# 2_MCU.net
KiCad netlist of a schematic drawn in Altium Designer
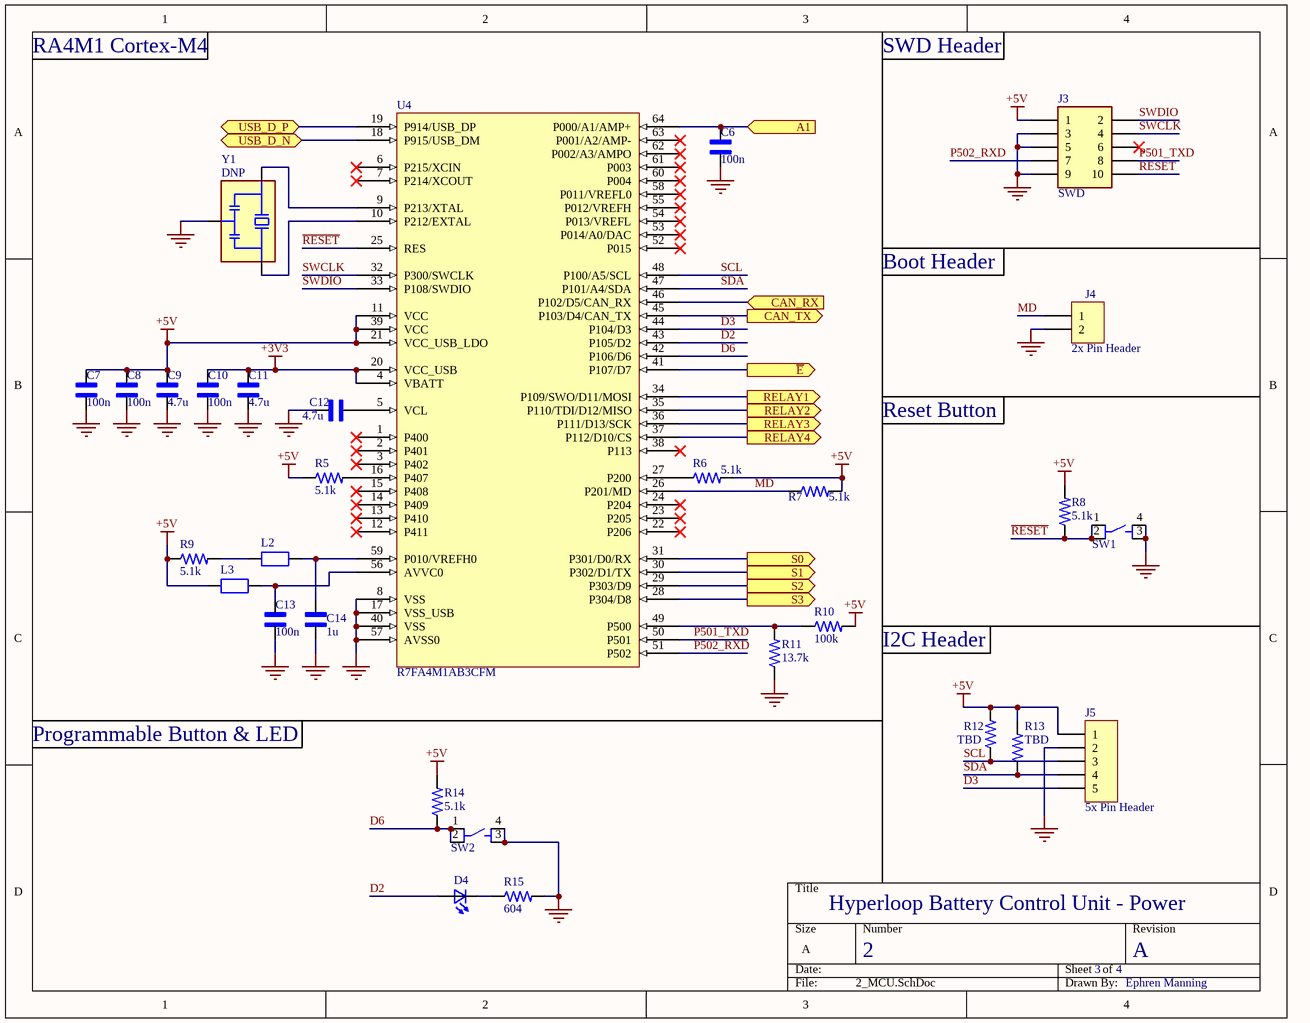
[diagram p0: 2_MCU.SchDoc]

(export (version "E")
  (design (tool "Eeschema 10.0.6"))
  (components
    (comp (ref "C6")
      (value "100n")
      (footprint "CAP_0603-Footprint")
      (description "100nF/16V ±10% Ceramic 0603")
      (libsource (lib "SAE @ UIC Formula Electric") (part "CAP_0603-Symbol"))
    )
    (comp (ref "C7")
      (value "100n")
      (footprint "CAP_0603-Footprint")
      (description "100nF/16V ±10% Ceramic 0603")
      (libsource (lib "SAE @ UIC Formula Electric") (part "CAP_0603-Symbol"))
    )
    (comp (ref "C8")
      (value "100n")
      (footprint "CAP_0603-Footprint")
      (description "100nF/16V ±10% Ceramic 0603")
      (libsource (lib "SAE @ UIC Formula Electric") (part "CAP_0603-Symbol"))
    )
    (comp (ref "C9")
      (value "4.7u")
      (footprint "CAP_0603-Footprint")
      (description "4.7uF/10V 0603 Ceramic Capacitor")
      (libsource (lib "SAE @ UIC Formula Electric") (part "CAP_0603-Symbol"))
    )
    (comp (ref "C10")
      (value "100n")
      (footprint "CAP_0603-Footprint")
      (description "100nF/16V ±10% Ceramic 0603")
      (libsource (lib "SAE @ UIC Formula Electric") (part "CAP_0603-Symbol"))
    )
    (comp (ref "C11")
      (value "4.7u")
      (footprint "CAP_0603-Footprint")
      (description "4.7uF/10V 0603 Ceramic Capacitor")
      (libsource (lib "SAE @ UIC Formula Electric") (part "CAP_0603-Symbol"))
    )
    (comp (ref "C12")
      (value "4.7u")
      (footprint "CAP_0603-Footprint")
      (description "4.7uF/10V 0603 Ceramic Capacitor")
      (libsource (lib "") (part "CAP_0603-Symbol_1"))
    )
    (comp (ref "C13")
      (value "100n")
      (footprint "CAP_0603-Footprint")
      (description "100nF/16V ±10% Ceramic 0603")
      (libsource (lib "SAE @ UIC Formula Electric") (part "CAP_0603-Symbol"))
    )
    (comp (ref "C14")
      (value "1u")
      (footprint "CAP_0603-Footprint")
      (description "1uF/10V ±10% 0603")
      (libsource (lib "SAE @ UIC Formula Electric") (part "CAP_0603-Symbol"))
    )
    (comp (ref "D4")
      (value "LTST-C191KGKT")
      (footprint "LED_0603-Footprint-1")
      (description "Green 571nm LED Indication - Discrete 2V 0603 (1608 Metric)")
      (libsource (lib "SAE @ UIC Formula Electric") (part "LTST-C191KGKT"))
    )
    (comp (ref "J3")
      (value "SWD")
      (footprint "CNC_3221-10-0100-00")
      (description "SWD Connector")
      (libsource (lib "SAE @ UIC Formula Electric") (part "3221-10-0100-00"))
    )
    (comp (ref "J4")
      (value "2x Pin Header")
      (footprint "2x Pin Header-Footprint-1")
      (libsource (lib "SAE @ UIC Formula Electric") (part "2x Pin Header-Symbol-1"))
    )
    (comp (ref "J5")
      (value "5x Pin Header")
      (footprint "5x Pin Header-Footprint-1")
      (libsource (lib "SAE @ UIC Formula Electric") (part "5x Pin Header-Symbol-1"))
    )
    (comp (ref "L2")
      (value "BLM18PG471SN1D")
      (footprint "BEADC1608X95N")
      (description "Ferrite Bead, 0603, 470 Ohms @ 100MHz")
      (libsource (lib "SAE @ UIC Formula Electric") (part "BLM18PG471SN1D"))
    )
    (comp (ref "L3")
      (value "BLM18PG471SN1D")
      (footprint "BEADC1608X95N")
      (description "Ferrite Bead, 0603, 470 Ohms @ 100MHz")
      (libsource (lib "SAE @ UIC Formula Electric") (part "BLM18PG471SN1D"))
    )
    (comp (ref "R5")
      (value "5.1k")
      (footprint "RES_0603-Footprint-1")
      (description "5.1k Ohms ±1% 0.1W 0603")
      (libsource (lib "SAE @ UIC Formula Electric") (part "0603_Res"))
    )
    (comp (ref "R6")
      (value "5.1k")
      (footprint "RES_0603-Footprint-1")
      (description "5.1k Ohms ±1% 0.1W 0603")
      (libsource (lib "SAE @ UIC Formula Electric") (part "0603_Res"))
    )
    (comp (ref "R7")
      (value "5.1k")
      (footprint "RES_0603-Footprint-1")
      (description "5.1k Ohms ±1% 0.1W 0603")
      (libsource (lib "SAE @ UIC Formula Electric") (part "0603_Res"))
    )
    (comp (ref "R8")
      (value "5.1k")
      (footprint "RES_0603-Footprint-1")
      (description "5.1k Ohms ±1% 0.1W 0603")
      (libsource (lib "SAE @ UIC Formula Electric") (part "0603_Res"))
    )
    (comp (ref "R9")
      (value "5.1k")
      (footprint "RES_0603-Footprint-1")
      (description "5.1k Ohms ±1% 0.1W 0603")
      (libsource (lib "SAE @ UIC Formula Electric") (part "0603_Res"))
    )
    (comp (ref "R10")
      (value "100k")
      (footprint "RES_0603-Footprint-1")
      (description "100k ±1% 0.1W, 0603")
      (libsource (lib "SAE @ UIC Formula Electric") (part "0603_Res"))
    )
    (comp (ref "R11")
      (value "13.7k")
      (footprint "RES_0603-Footprint-1")
      (description "13.7K 1% 0,1W 0603")
      (libsource (lib "SAE @ UIC Formula Electric") (part "0603_Res"))
    )
    (comp (ref "R12")
      (value "TBD")
      (footprint "RES_0603-Footprint-1")
      (description "5.1k Ohms ±1% 0.1W 0603")
      (libsource (lib "SAE @ UIC Formula Electric") (part "0603_Res"))
    )
    (comp (ref "R13")
      (value "TBD")
      (footprint "RES_0603-Footprint-1")
      (description "5.1k Ohms ±1% 0.1W 0603")
      (libsource (lib "SAE @ UIC Formula Electric") (part "0603_Res"))
    )
    (comp (ref "R14")
      (value "5.1k")
      (footprint "RES_0603-Footprint-1")
      (description "5.1k Ohms ±1% 0.1W 0603")
      (libsource (lib "SAE @ UIC Formula Electric") (part "0603_Res"))
    )
    (comp (ref "R15")
      (value "604")
      (footprint "RES_0603-Footprint-1")
      (description "604 Ohm 1% 1/10 W 0603")
      (libsource (lib "SAE @ UIC Formula Electric") (part "0603_Res"))
    )
    (comp (ref "SW1")
      (value "PTS810_SJM_250_SMTR_LFS")
      (footprint "SW_PTS810_SJM_250_SMTR_LFS")
      (description "Tactile Switch SPST-NO Top Actuated Surface Mount")
      (libsource (lib "SAE @ UIC Formula Electric") (part "PTS810_SJM_250_SMTR_LFS"))
    )
    (comp (ref "SW2")
      (value "PTS810_SJM_250_SMTR_LFS")
      (footprint "SW_PTS810_SJM_250_SMTR_LFS")
      (description "Tactile Switch SPST-NO Top Actuated Surface Mount")
      (libsource (lib "SAE @ UIC Formula Electric") (part "PTS810_SJM_250_SMTR_LFS"))
    )
    (comp (ref "U4")
      (value "R7FA4M1AB3CFM")
      (footprint "R7FA4M1AB3CFM-Footprint-1")
      (description "RA4M1 Cortex-M4 Microcontroller 64-LQFP")
      (libsource (lib "SAE @ UIC Formula Electric") (part "R7FA4M1AB3CFM-Symbol-1"))
    )
    (comp (ref "Y1")
      (value "DNP")
      (footprint "OSC_CSTNE12M0G55Z000R0")
      (description "12MHz Ceramic Resonator Built in Capacitor 33pF ±0.2% 30 Ohms Surface Mount")
      (libsource (lib "SAE @ UIC Formula Electric") (part "CSTNE12M0G55Z000R0"))
    )
  )
  (nets
    (net (code "1") (name "+3V3") (class "Default")
      (node (ref "C10") (pin "2") (pinfunction "2_2") (pintype "passive"))
      (node (ref "C11") (pin "2") (pinfunction "2_2") (pintype "passive"))
      (node (ref "U4") (pin "20") (pinfunction "VCC_USB_20") (pintype "input"))
      (node (ref "U4") (pin "4") (pinfunction "VBATT_4") (pintype "input"))
    )
    (net (code "2") (name "+5V") (class "Default")
      (node (ref "C7") (pin "2") (pinfunction "2_2") (pintype "passive"))
      (node (ref "C8") (pin "2") (pinfunction "2_2") (pintype "passive"))
      (node (ref "C9") (pin "2") (pinfunction "2_2") (pintype "passive"))
      (node (ref "J3") (pin "1") (pinfunction "1_1") (pintype "passive"))
      (node (ref "J5") (pin "1") (pinfunction "1_1") (pintype "passive"))
      (node (ref "L3") (pin "1") (pinfunction "1_1") (pintype "passive"))
      (node (ref "R10") (pin "2") (pinfunction "2_2") (pintype "passive"))
      (node (ref "R12") (pin "2") (pinfunction "2_2") (pintype "passive"))
      (node (ref "R13") (pin "2") (pinfunction "2_2") (pintype "passive"))
      (node (ref "R14") (pin "2") (pinfunction "2_2") (pintype "passive"))
      (node (ref "R5") (pin "1") (pinfunction "1_1") (pintype "passive"))
      (node (ref "R6") (pin "2") (pinfunction "2_2") (pintype "passive"))
      (node (ref "R7") (pin "2") (pinfunction "2_2") (pintype "passive"))
      (node (ref "R8") (pin "2") (pinfunction "2_2") (pintype "passive"))
      (node (ref "R9") (pin "1") (pinfunction "1_1") (pintype "passive"))
      (node (ref "U4") (pin "11") (pinfunction "VCC_11") (pintype "input"))
      (node (ref "U4") (pin "21") (pinfunction "VCC_USB_LDO_21") (pintype "input"))
      (node (ref "U4") (pin "39") (pinfunction "VCC_39") (pintype "input"))
    )
    (net (code "3") (name "/A1") (class "Default")
      (node (ref "C6") (pin "2") (pinfunction "2_2") (pintype "passive"))
      (node (ref "U4") (pin "64") (pinfunction "P000/A1/AMP+_64") (pintype "input"))
    )
    (net (code "4") (name "/CAN_RX") (class "Default")
      (node (ref "U4") (pin "46") (pinfunction "P102/D5/CAN_RX_46") (pintype "input"))
    )
    (net (code "5") (name "/CAN_TX") (class "Default")
      (node (ref "U4") (pin "45") (pinfunction "P103/D4/CAN_TX_45") (pintype "input"))
    )
    (net (code "6") (name "/D2") (class "Default")
      (node (ref "D4") (pin "2") (pinfunction "A2_2") (pintype "passive"))
      (node (ref "U4") (pin "43") (pinfunction "P105/D2_43") (pintype "input"))
    )
    (net (code "7") (name "/D3") (class "Default")
      (node (ref "J5") (pin "5") (pinfunction "5_5") (pintype "passive"))
      (node (ref "U4") (pin "44") (pinfunction "P104/D3_44") (pintype "input"))
    )
    (net (code "8") (name "/D6") (class "Default")
      (node (ref "R14") (pin "1") (pinfunction "1_1") (pintype "passive"))
      (node (ref "SW2") (pin "1") (pinfunction "1_1") (pintype "passive"))
      (node (ref "SW2") (pin "2") (pinfunction "2_2") (pintype "passive"))
      (node (ref "U4") (pin "42") (pinfunction "P106/D6_42") (pintype "input"))
    )
    (net (code "9") (name "/MD") (class "Default")
      (node (ref "J4") (pin "1") (pinfunction "1_1") (pintype "passive"))
      (node (ref "R7") (pin "1") (pinfunction "1_1") (pintype "passive"))
      (node (ref "U4") (pin "26") (pinfunction "P201/MD_26") (pintype "input"))
    )
    (net (code "10") (name "/P501_TXD") (class "Default")
      (node (ref "J3") (pin "8") (pinfunction "8_8") (pintype "passive"))
      (node (ref "U4") (pin "50") (pinfunction "P501_50") (pintype "input"))
    )
    (net (code "11") (name "/P502_RXD") (class "Default")
      (node (ref "J3") (pin "7") (pinfunction "7_7") (pintype "passive"))
      (node (ref "U4") (pin "51") (pinfunction "P502_51") (pintype "input"))
    )
    (net (code "12") (name "/RELAY1") (class "Default")
      (node (ref "U4") (pin "34") (pinfunction "P109/SWO/D11/MOSI_34") (pintype "input"))
    )
    (net (code "13") (name "/RELAY2") (class "Default")
      (node (ref "U4") (pin "35") (pinfunction "P110/TDI/D12/MISO_35") (pintype "input"))
    )
    (net (code "14") (name "/RELAY3") (class "Default")
      (node (ref "U4") (pin "36") (pinfunction "P111/D13/SCK_36") (pintype "input"))
    )
    (net (code "15") (name "/RELAY4") (class "Default")
      (node (ref "U4") (pin "37") (pinfunction "P112/D10/CS_37") (pintype "input"))
    )
    (net (code "16") (name "/S0") (class "Default")
      (node (ref "U4") (pin "31") (pinfunction "P301/D0/RX_31") (pintype "input"))
    )
    (net (code "17") (name "/S1") (class "Default")
      (node (ref "U4") (pin "30") (pinfunction "P302/D1/TX_30") (pintype "input"))
    )
    (net (code "18") (name "/S2") (class "Default")
      (node (ref "U4") (pin "29") (pinfunction "P303/D9_29") (pintype "input"))
    )
    (net (code "19") (name "/S3") (class "Default")
      (node (ref "U4") (pin "28") (pinfunction "P304/D8_28") (pintype "input"))
    )
    (net (code "20") (name "/SCL") (class "Default")
      (node (ref "J5") (pin "3") (pinfunction "3_3") (pintype "passive"))
      (node (ref "R12") (pin "1") (pinfunction "1_1") (pintype "passive"))
      (node (ref "U4") (pin "48") (pinfunction "P100/A5/SCL_48") (pintype "input"))
    )
    (net (code "21") (name "/SDA") (class "Default")
      (node (ref "J5") (pin "4") (pinfunction "4_4") (pintype "passive"))
      (node (ref "R13") (pin "1") (pinfunction "1_1") (pintype "passive"))
      (node (ref "U4") (pin "47") (pinfunction "P101/A4/SDA_47") (pintype "input"))
    )
    (net (code "22") (name "/SWCLK") (class "Default")
      (node (ref "J3") (pin "4") (pinfunction "4_4") (pintype "passive"))
      (node (ref "U4") (pin "32") (pinfunction "P300/SWCLK_32") (pintype "input"))
    )
    (net (code "23") (name "/SWDIO") (class "Default")
      (node (ref "J3") (pin "2") (pinfunction "2_2") (pintype "passive"))
      (node (ref "U4") (pin "33") (pinfunction "P108/SWDIO_33") (pintype "input"))
    )
    (net (code "24") (name "/USB_D_N") (class "Default")
      (node (ref "U4") (pin "18") (pinfunction "P915/USB_DM_18") (pintype "input"))
    )
    (net (code "25") (name "/USB_D_P") (class "Default")
      (node (ref "U4") (pin "19") (pinfunction "P914/USB_DP_19") (pintype "input"))
    )
    (net (code "26") (name "/~{E}") (class "Default")
      (node (ref "U4") (pin "41") (pinfunction "P107/D7_41") (pintype "input"))
    )
    (net (code "27") (name "/~{RESET}") (class "Default")
      (node (ref "J3") (pin "10") (pinfunction "10_10") (pintype "passive"))
      (node (ref "R8") (pin "1") (pinfunction "1_1") (pintype "passive"))
      (node (ref "SW1") (pin "1") (pinfunction "1_1") (pintype "passive"))
      (node (ref "SW1") (pin "2") (pinfunction "2_2") (pintype "passive"))
      (node (ref "U4") (pin "25") (pinfunction "RES_25") (pintype "input"))
    )
    (net (code "28") (name "GND") (class "Default")
      (node (ref "C10") (pin "1") (pinfunction "1_1") (pintype "passive"))
      (node (ref "C11") (pin "1") (pinfunction "1_1") (pintype "passive"))
      (node (ref "C12") (pin "1") (pinfunction "1_1") (pintype "passive"))
      (node (ref "C13") (pin "1") (pinfunction "1_1") (pintype "passive"))
      (node (ref "C14") (pin "1") (pinfunction "1_1") (pintype "passive"))
      (node (ref "C6") (pin "1") (pinfunction "1_1") (pintype "passive"))
      (node (ref "C7") (pin "1") (pinfunction "1_1") (pintype "passive"))
      (node (ref "C8") (pin "1") (pinfunction "1_1") (pintype "passive"))
      (node (ref "C9") (pin "1") (pinfunction "1_1") (pintype "passive"))
      (node (ref "J3") (pin "3") (pinfunction "3_3") (pintype "passive"))
      (node (ref "J3") (pin "5") (pinfunction "5_5") (pintype "passive"))
      (node (ref "J3") (pin "9") (pinfunction "9_9") (pintype "passive"))
      (node (ref "J4") (pin "2") (pinfunction "2_2") (pintype "passive"))
      (node (ref "J5") (pin "2") (pinfunction "2_2") (pintype "passive"))
      (node (ref "R11") (pin "1") (pinfunction "1_1") (pintype "passive"))
      (node (ref "R15") (pin "2") (pinfunction "2_2") (pintype "passive"))
      (node (ref "SW1") (pin "3") (pinfunction "3_3") (pintype "passive"))
      (node (ref "SW1") (pin "4") (pinfunction "4_4") (pintype "passive"))
      (node (ref "SW2") (pin "3") (pinfunction "3_3") (pintype "passive"))
      (node (ref "SW2") (pin "4") (pinfunction "4_4") (pintype "passive"))
      (node (ref "U4") (pin "17") (pinfunction "VSS_USB_17") (pintype "input"))
      (node (ref "U4") (pin "40") (pinfunction "VSS_40") (pintype "input"))
      (node (ref "U4") (pin "57") (pinfunction "AVSS0_57") (pintype "input"))
      (node (ref "U4") (pin "8") (pinfunction "VSS_8") (pintype "input"))
      (node (ref "Y1") (pin "2") (pinfunction "GND_2") (pintype "power_in"))
    )
    (net (code "29") (name "Net-(D4-K2)") (class "Default")
      (node (ref "D4") (pin "1") (pinfunction "K2_1") (pintype "passive"))
      (node (ref "R15") (pin "1") (pinfunction "1_1") (pintype "passive"))
    )
    (net (code "30") (name "Net-(L2-Pad1)") (class "Default")
      (node (ref "L2") (pin "1") (pinfunction "1_1") (pintype "passive"))
      (node (ref "R9") (pin "2") (pinfunction "2_2") (pintype "passive"))
    )
    (net (code "31") (name "Net-(U4-AVVC0)") (class "Default")
      (node (ref "C13") (pin "2") (pinfunction "2_2") (pintype "passive"))
      (node (ref "L3") (pin "2") (pinfunction "2_2") (pintype "passive"))
      (node (ref "U4") (pin "56") (pinfunction "AVVC0_56") (pintype "input"))
    )
    (net (code "32") (name "Net-(U4-P010{slash}VREFH0)") (class "Default")
      (node (ref "C14") (pin "2") (pinfunction "2_2") (pintype "passive"))
      (node (ref "L2") (pin "2") (pinfunction "2_2") (pintype "passive"))
      (node (ref "U4") (pin "59") (pinfunction "P010/VREFH0_59") (pintype "input"))
    )
    (net (code "33") (name "Net-(U4-P200)") (class "Default")
      (node (ref "R6") (pin "1") (pinfunction "1_1") (pintype "passive"))
      (node (ref "U4") (pin "27") (pinfunction "P200_27") (pintype "input"))
    )
    (net (code "34") (name "Net-(U4-P212{slash}EXTAL)") (class "Default")
      (node (ref "U4") (pin "10") (pinfunction "P212/EXTAL_10") (pintype "input"))
      (node (ref "Y1") (pin "3") (pinfunction "OUT_3") (pintype "passive"))
    )
    (net (code "35") (name "Net-(U4-P213{slash}XTAL)") (class "Default")
      (node (ref "U4") (pin "9") (pinfunction "P213/XTAL_9") (pintype "input"))
      (node (ref "Y1") (pin "1") (pinfunction "IN_1") (pintype "passive"))
    )
    (net (code "36") (name "Net-(U4-P407)") (class "Default")
      (node (ref "R5") (pin "2") (pinfunction "2_2") (pintype "passive"))
      (node (ref "U4") (pin "16") (pinfunction "P407_16") (pintype "input"))
    )
    (net (code "37") (name "Net-(U4-P500)") (class "Default")
      (node (ref "R10") (pin "1") (pinfunction "1_1") (pintype "passive"))
      (node (ref "R11") (pin "2") (pinfunction "2_2") (pintype "passive"))
      (node (ref "U4") (pin "49") (pinfunction "P500_49") (pintype "input"))
    )
    (net (code "38") (name "Net-(U4-VCL)") (class "Default")
      (node (ref "C12") (pin "2") (pinfunction "2_2") (pintype "passive"))
      (node (ref "U4") (pin "5") (pinfunction "VCL_5") (pintype "input"))
    )
    (net (code "39") (name "unconnected-(J3-Pad6)") (class "Default")
      (node (ref "J3") (pin "6") (pinfunction "6_6") (pintype "passive+no_connect"))
    )
    (net (code "40") (name "unconnected-(U4-P001{slash}A2{slash}AMP--Pad63)") (class "Default")
      (node (ref "U4") (pin "63") (pinfunction "P001/A2/AMP-_63") (pintype "input+no_connect"))
    )
    (net (code "41") (name "unconnected-(U4-P002{slash}A3{slash}AMPO-Pad62)") (class "Default")
      (node (ref "U4") (pin "62") (pinfunction "P002/A3/AMPO_62") (pintype "input+no_connect"))
    )
    (net (code "42") (name "unconnected-(U4-P003-Pad61)") (class "Default")
      (node (ref "U4") (pin "61") (pinfunction "P003_61") (pintype "input+no_connect"))
    )
    (net (code "43") (name "unconnected-(U4-P004-Pad60)") (class "Default")
      (node (ref "U4") (pin "60") (pinfunction "P004_60") (pintype "input+no_connect"))
    )
    (net (code "44") (name "unconnected-(U4-P011{slash}VREFL0-Pad58)") (class "Default")
      (node (ref "U4") (pin "58") (pinfunction "P011/VREFL0_58") (pintype "input+no_connect"))
    )
    (net (code "45") (name "unconnected-(U4-P012{slash}VREFH-Pad55)") (class "Default")
      (node (ref "U4") (pin "55") (pinfunction "P012/VREFH_55") (pintype "input+no_connect"))
    )
    (net (code "46") (name "unconnected-(U4-P013{slash}VREFL-Pad54)") (class "Default")
      (node (ref "U4") (pin "54") (pinfunction "P013/VREFL_54") (pintype "input+no_connect"))
    )
    (net (code "47") (name "unconnected-(U4-P014{slash}A0{slash}DAC-Pad53)") (class "Default")
      (node (ref "U4") (pin "53") (pinfunction "P014/A0/DAC_53") (pintype "input+no_connect"))
    )
    (net (code "48") (name "unconnected-(U4-P015-Pad52)") (class "Default")
      (node (ref "U4") (pin "52") (pinfunction "P015_52") (pintype "input+no_connect"))
    )
    (net (code "49") (name "unconnected-(U4-P113-Pad38)") (class "Default")
      (node (ref "U4") (pin "38") (pinfunction "P113_38") (pintype "input+no_connect"))
    )
    (net (code "50") (name "unconnected-(U4-P204-Pad24)") (class "Default")
      (node (ref "U4") (pin "24") (pinfunction "P204_24") (pintype "input+no_connect"))
    )
    (net (code "51") (name "unconnected-(U4-P205-Pad23)") (class "Default")
      (node (ref "U4") (pin "23") (pinfunction "P205_23") (pintype "input+no_connect"))
    )
    (net (code "52") (name "unconnected-(U4-P206-Pad22)") (class "Default")
      (node (ref "U4") (pin "22") (pinfunction "P206_22") (pintype "input+no_connect"))
    )
    (net (code "53") (name "unconnected-(U4-P214{slash}XCOUT-Pad7)") (class "Default")
      (node (ref "U4") (pin "7") (pinfunction "P214/XCOUT_7") (pintype "input+no_connect"))
    )
    (net (code "54") (name "unconnected-(U4-P215{slash}XCIN-Pad6)") (class "Default")
      (node (ref "U4") (pin "6") (pinfunction "P215/XCIN_6") (pintype "input+no_connect"))
    )
    (net (code "55") (name "unconnected-(U4-P400-Pad1)") (class "Default")
      (node (ref "U4") (pin "1") (pinfunction "P400_1") (pintype "input+no_connect"))
    )
    (net (code "56") (name "unconnected-(U4-P401-Pad2)") (class "Default")
      (node (ref "U4") (pin "2") (pinfunction "P401_2") (pintype "input+no_connect"))
    )
    (net (code "57") (name "unconnected-(U4-P402-Pad3)") (class "Default")
      (node (ref "U4") (pin "3") (pinfunction "P402_3") (pintype "input+no_connect"))
    )
    (net (code "58") (name "unconnected-(U4-P408-Pad15)") (class "Default")
      (node (ref "U4") (pin "15") (pinfunction "P408_15") (pintype "input+no_connect"))
    )
    (net (code "59") (name "unconnected-(U4-P409-Pad14)") (class "Default")
      (node (ref "U4") (pin "14") (pinfunction "P409_14") (pintype "input+no_connect"))
    )
    (net (code "60") (name "unconnected-(U4-P410-Pad13)") (class "Default")
      (node (ref "U4") (pin "13") (pinfunction "P410_13") (pintype "input+no_connect"))
    )
    (net (code "61") (name "unconnected-(U4-P411-Pad12)") (class "Default")
      (node (ref "U4") (pin "12") (pinfunction "P411_12") (pintype "input+no_connect"))
    )
  )
)
